# OpenEarable-PCB-flex-2_0.net
KiCad netlist of a schematic drawn in EasyEDA Pro
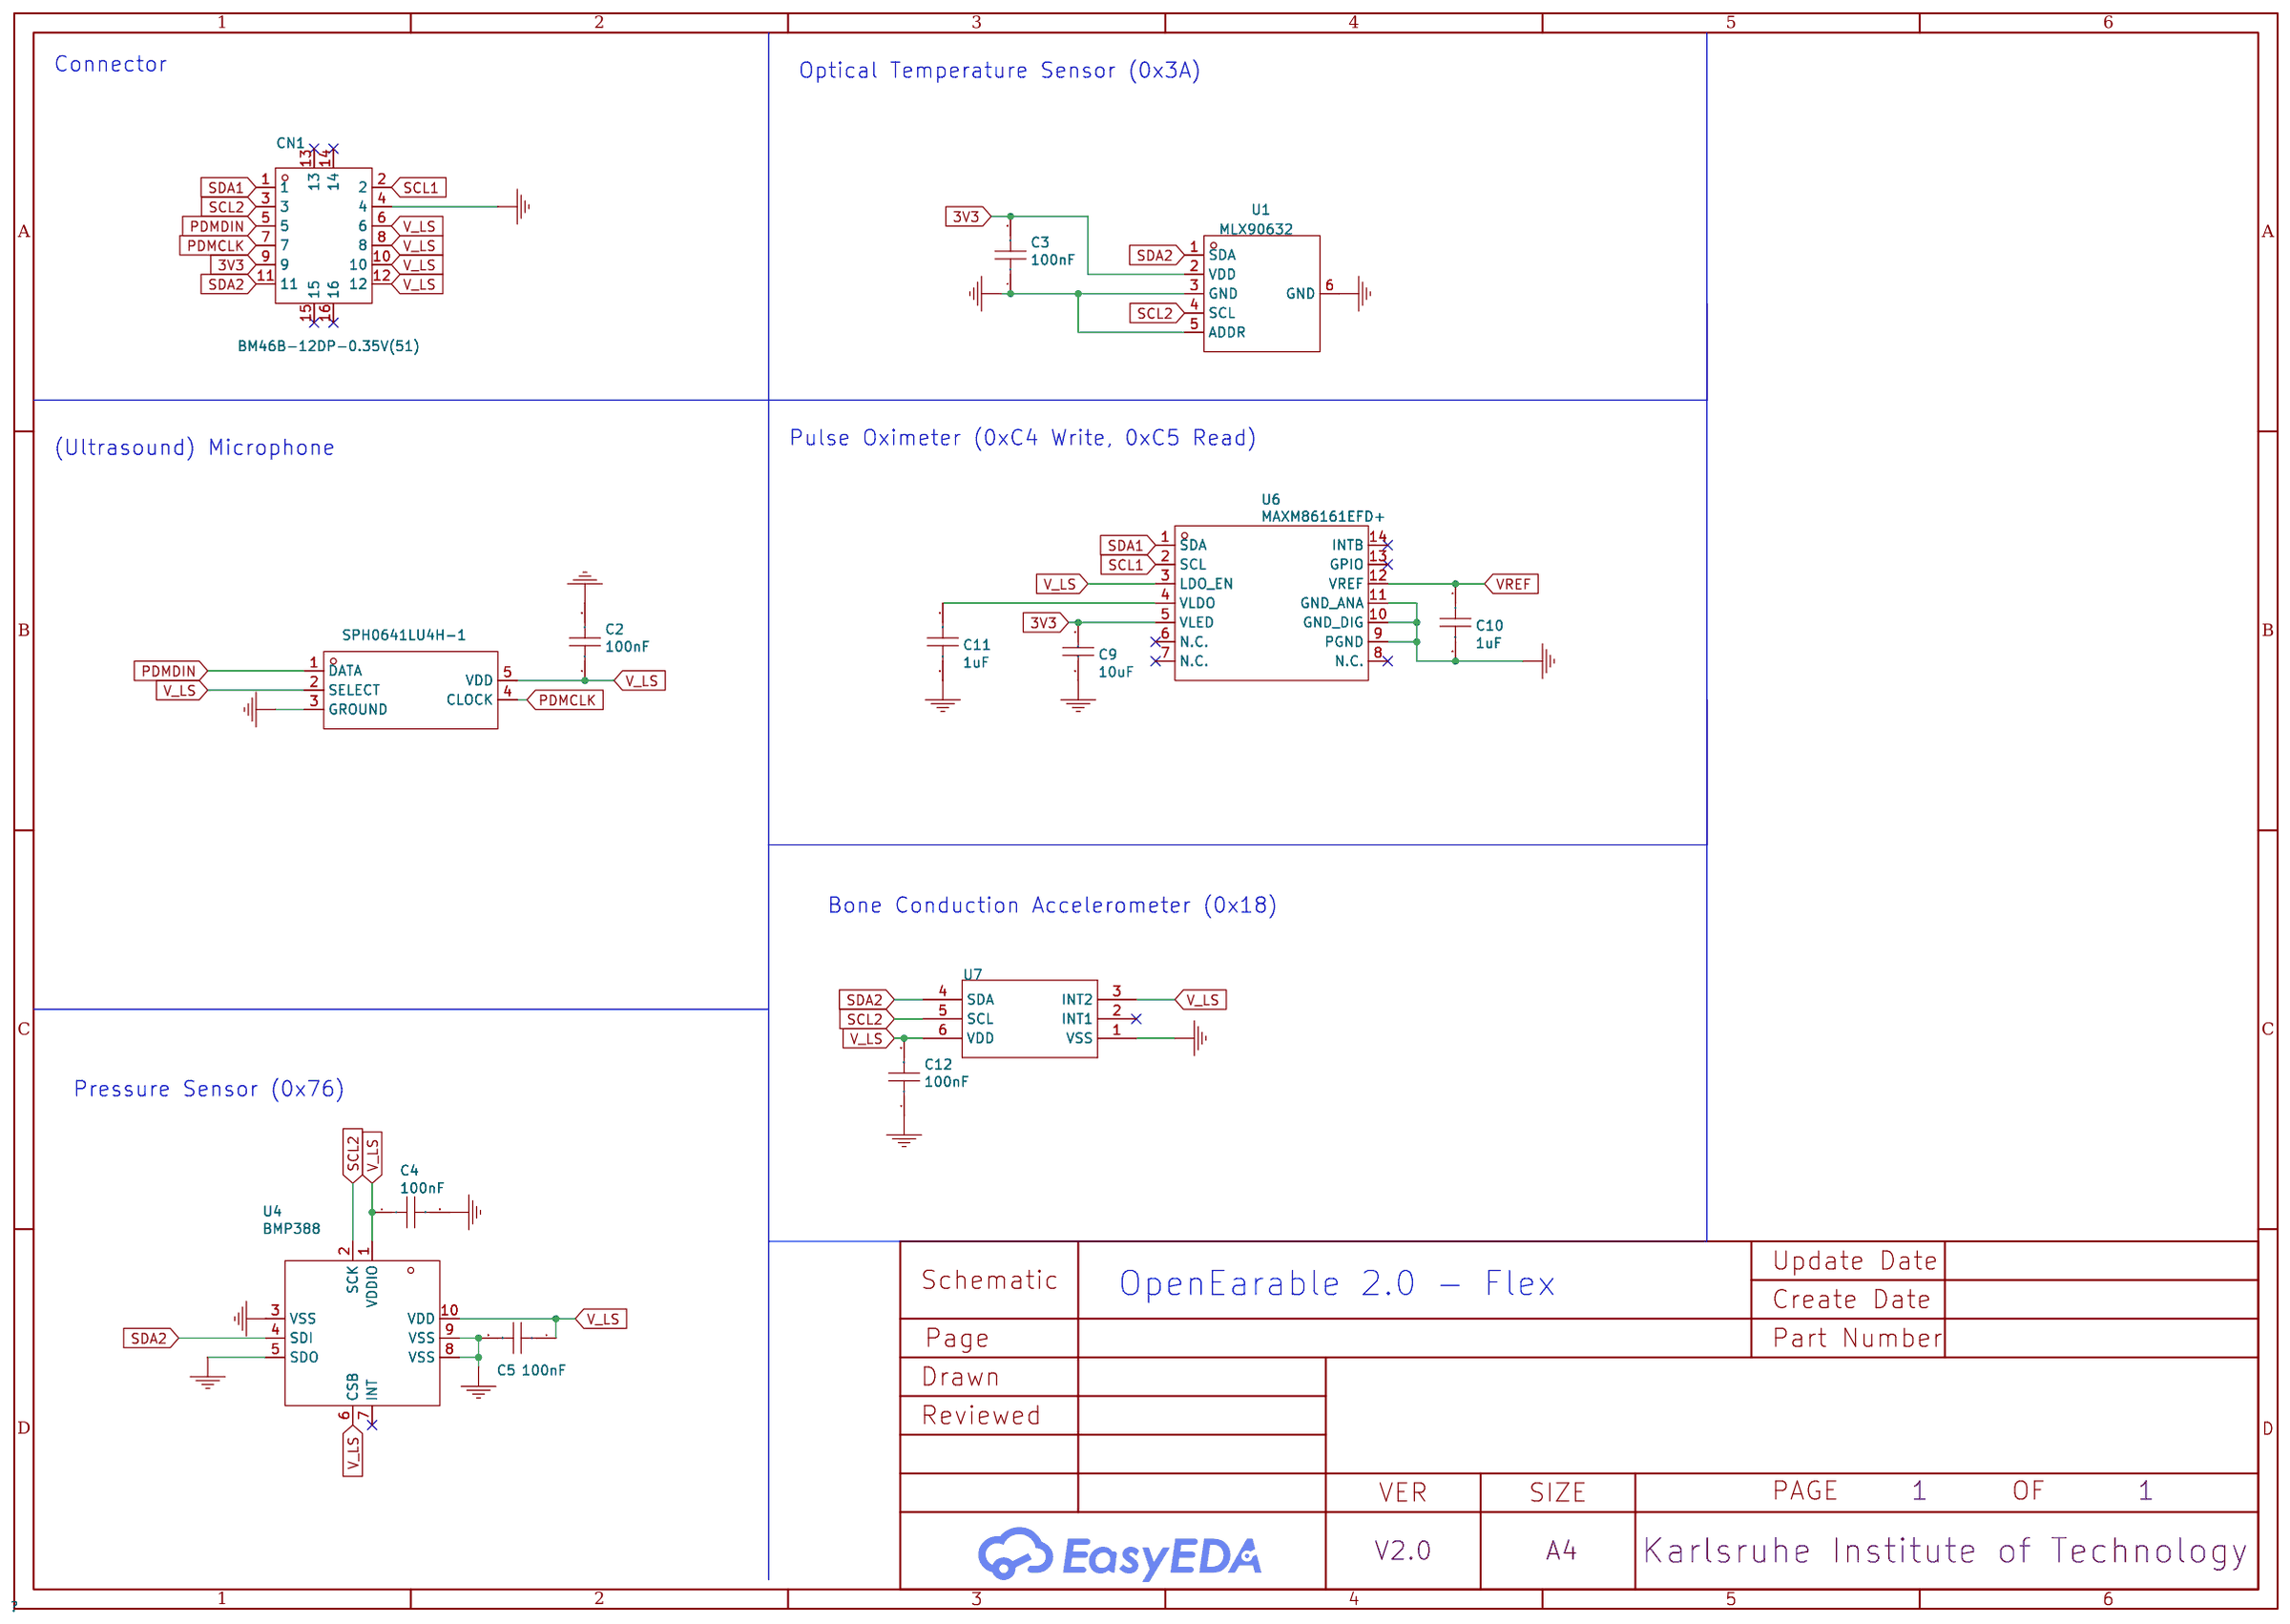
[diagram p0: schematic sheet]

(export (version "E")
  (design (tool "Eeschema 10.0.6"))
  (components
    (comp (ref "C2")
      (value "100nF")
      (footprint "easyedapro:C0201")
      (fields
        (field (name "Manufacturer Part") "TCC0201X5R104M6R3ZT")
        (field (name "Manufacturer") "CCTC(三环)")
      )
      (libsource (lib "easyedapro") (part "100nF"))
    )
    (comp (ref "C3")
      (value "100nF")
      (footprint "easyedapro:C0201")
      (fields
        (field (name "Manufacturer Part") "TCC0201X5R104M6R3ZT")
        (field (name "Manufacturer") "CCTC(三环)")
      )
      (libsource (lib "easyedapro") (part "100nF"))
    )
    (comp (ref "C4")
      (value "100nF")
      (footprint "easyedapro:C0201")
      (fields
        (field (name "Manufacturer Part") "TCC0201X5R104M6R3ZT")
        (field (name "Manufacturer") "CCTC(三环)")
      )
      (libsource (lib "easyedapro") (part "100nF"))
    )
    (comp (ref "C5")
      (value "100nF")
      (footprint "easyedapro:C0201")
      (fields
        (field (name "Manufacturer Part") "TCC0201X5R104M6R3ZT")
        (field (name "Manufacturer") "CCTC(三环)")
      )
      (libsource (lib "easyedapro") (part "100nF"))
    )
    (comp (ref "C9")
      (value "10uF")
      (footprint "easyedapro:C0402")
      (fields
        (field (name "Manufacturer Part") "CL05A106MQ5NUNC")
        (field (name "Manufacturer") "SAMSUNG(三星)")
      )
      (libsource (lib "easyedapro") (part "10uF"))
    )
    (comp (ref "C10")
      (value "1uF")
      (footprint "easyedapro:C0201")
      (fields
        (field (name "Manufacturer Part") "C0201X5R105M6R3NT")
        (field (name "Manufacturer") "SANYEAR(叁叶源)")
      )
      (libsource (lib "easyedapro") (part "1uF"))
    )
    (comp (ref "C11")
      (value "1uF")
      (footprint "easyedapro:C0201")
      (fields
        (field (name "Manufacturer Part") "C0201X5R105M6R3NT")
        (field (name "Manufacturer") "SANYEAR(叁叶源)")
      )
      (libsource (lib "easyedapro") (part "1uF"))
    )
    (comp (ref "C12")
      (value "100nF")
      (footprint "easyedapro:C0201")
      (fields
        (field (name "Manufacturer Part") "TCC0201X5R104M6R3ZT")
        (field (name "Manufacturer") "CCTC(三环)")
      )
      (libsource (lib "easyedapro") (part "100nF"))
    )
    (comp (ref "CN1")
      (value "BM46B-12DP-0.35V(51)")
      (footprint "easyedapro:CONN-SMD_12P-P0.35_BM46B-12DP-0.35V-51")
      (description "Number of Pins:- Pitch:0.35mm Mounting Style:Standing paste Number of Rows:2 Contact Plating:Gold")
      (fields (field (name "Manufacturer") "HRS(广濑)"))
      (libsource (lib "easyedapro") (part "BM46B-12DP-0.35V(51)"))
    )
    (comp (ref "U1")
      (value "MLX90632")
      (footprint "easyedapro:SENSOR-SMD_MLX90632")
      (libsource (lib "easyedapro") (part "MLX90632"))
    )
    (comp (ref "U3")
      (value "SPH0641LU4H-1")
      (footprint "easyedapro:MIC-SMD_5P_L3.5-W2.7-P0.82_SPH0641LU4H-1")
      (fields (field (name "Manufacturer Part") "sph0641lu4h-1"))
      (libsource (lib "easyedapro") (part "SPH0641LU4H-1"))
    )
    (comp (ref "U4")
      (value "BMP388")
      (footprint "easyedapro:SENSORM-SMD_BMP388")
      (fields (field (name "Manufacturer") "Bosch(博世)"))
      (libsource (lib "easyedapro") (part "BMP388"))
    )
    (comp (ref "U6")
      (value "MAXM86161EFD+")
      (footprint "easyedapro:OLGA-14_L4.3-W2.9-P0.60-TL")
      (fields (field (name "Manufacturer") "MAXIM(美信)"))
      (libsource (lib "easyedapro") (part "MAXM86161EFD+"))
    )
    (comp (ref "U7")
      (value "~")
      (footprint "easyedapro:BMA580")
      (libsource (lib "easyedapro") (part "BMA580"))
    )
  )
  (nets
    (net (code "1") (name "3V3") (class "Default")
      (node (ref "C3") (pin "2") (pinfunction "2_2") (pintype "unspecified"))
      (node (ref "C9") (pin "1") (pinfunction "1_1") (pintype "input"))
      (node (ref "CN1") (pin "9") (pinfunction "9_9") (pintype "unspecified"))
      (node (ref "U1") (pin "2") (pinfunction "VDD_2") (pintype "unspecified"))
      (node (ref "U6") (pin "5") (pinfunction "VLED_5") (pintype "unspecified"))
    )
    (net (code "2") (name "GND") (class "Default")
      (node (ref "C10") (pin "2") (pinfunction "2_2") (pintype "unspecified"))
      (node (ref "C11") (pin "2") (pinfunction "2_2") (pintype "unspecified"))
      (node (ref "C12") (pin "1") (pinfunction "1_1") (pintype "unspecified"))
      (node (ref "C2") (pin "2") (pinfunction "2_2") (pintype "unspecified"))
      (node (ref "C3") (pin "1") (pinfunction "1_1") (pintype "unspecified"))
      (node (ref "C4") (pin "2") (pinfunction "2_2") (pintype "unspecified"))
      (node (ref "C5") (pin "2") (pinfunction "2_2") (pintype "unspecified"))
      (node (ref "C9") (pin "2") (pinfunction "2_2") (pintype "input"))
      (node (ref "CN1") (pin "4") (pinfunction "4_4") (pintype "unspecified"))
      (node (ref "U1") (pin "3") (pinfunction "GND_3") (pintype "unspecified"))
      (node (ref "U1") (pin "5") (pinfunction "ADDR_5") (pintype "unspecified"))
      (node (ref "U1") (pin "6") (pinfunction "GND_6") (pintype "unspecified"))
      (node (ref "U3") (pin "3") (pinfunction "GROUND_3") (pintype "unspecified"))
      (node (ref "U4") (pin "3") (pinfunction "VSS_3") (pintype "unspecified"))
      (node (ref "U4") (pin "5") (pinfunction "SDO_5") (pintype "unspecified"))
      (node (ref "U4") (pin "8") (pinfunction "VSS_8") (pintype "unspecified"))
      (node (ref "U4") (pin "9") (pinfunction "VSS_9") (pintype "unspecified"))
      (node (ref "U6") (pin "10") (pinfunction "GND_DIG_10") (pintype "unspecified"))
      (node (ref "U6") (pin "11") (pinfunction "GND_ANA_11") (pintype "unspecified"))
      (node (ref "U6") (pin "9") (pinfunction "PGND_9") (pintype "unspecified"))
      (node (ref "U7") (pin "1") (pinfunction "VSS_1") (pintype "bidirectional"))
    )
    (net (code "3") (name "Net-(U6-VLDO)") (class "Default")
      (node (ref "C11") (pin "1") (pinfunction "1_1") (pintype "unspecified"))
      (node (ref "U6") (pin "4") (pinfunction "VLDO_4") (pintype "unspecified"))
    )
    (net (code "4") (name "PDMCLK") (class "Default")
      (node (ref "CN1") (pin "7") (pinfunction "7_7") (pintype "unspecified"))
      (node (ref "U3") (pin "4") (pinfunction "CLOCK_4") (pintype "unspecified"))
    )
    (net (code "5") (name "PDMDIN") (class "Default")
      (node (ref "CN1") (pin "5") (pinfunction "5_5") (pintype "unspecified"))
      (node (ref "U3") (pin "1") (pinfunction "DATA_1") (pintype "unspecified"))
    )
    (net (code "6") (name "SCL1") (class "Default")
      (node (ref "CN1") (pin "2") (pinfunction "2_2") (pintype "unspecified"))
      (node (ref "U6") (pin "2") (pinfunction "SCL_2") (pintype "unspecified"))
    )
    (net (code "7") (name "SCL2") (class "Default")
      (node (ref "CN1") (pin "3") (pinfunction "3_3") (pintype "unspecified"))
      (node (ref "U1") (pin "4") (pinfunction "SCL_4") (pintype "unspecified"))
      (node (ref "U4") (pin "2") (pinfunction "SCK_2") (pintype "unspecified"))
      (node (ref "U7") (pin "5") (pinfunction "SCL_5") (pintype "bidirectional"))
    )
    (net (code "8") (name "SDA1") (class "Default")
      (node (ref "CN1") (pin "1") (pinfunction "1_1") (pintype "unspecified"))
      (node (ref "U6") (pin "1") (pinfunction "SDA_1") (pintype "unspecified"))
    )
    (net (code "9") (name "SDA2") (class "Default")
      (node (ref "CN1") (pin "11") (pinfunction "11_11") (pintype "unspecified"))
      (node (ref "U1") (pin "1") (pinfunction "SDA_1") (pintype "unspecified"))
      (node (ref "U4") (pin "4") (pinfunction "SDI_4") (pintype "unspecified"))
      (node (ref "U7") (pin "4") (pinfunction "SDA_4") (pintype "bidirectional"))
    )
    (net (code "10") (name "VREF") (class "Default")
      (node (ref "C10") (pin "1") (pinfunction "1_1") (pintype "unspecified"))
      (node (ref "U6") (pin "12") (pinfunction "VREF_12") (pintype "unspecified"))
    )
    (net (code "11") (name "V_LS") (class "Default")
      (node (ref "C12") (pin "2") (pinfunction "2_2") (pintype "unspecified"))
      (node (ref "C2") (pin "1") (pinfunction "1_1") (pintype "unspecified"))
      (node (ref "C4") (pin "1") (pinfunction "1_1") (pintype "unspecified"))
      (node (ref "C5") (pin "1") (pinfunction "1_1") (pintype "unspecified"))
      (node (ref "CN1") (pin "10") (pinfunction "10_10") (pintype "unspecified"))
      (node (ref "CN1") (pin "12") (pinfunction "12_12") (pintype "unspecified"))
      (node (ref "CN1") (pin "6") (pinfunction "6_6") (pintype "unspecified"))
      (node (ref "CN1") (pin "8") (pinfunction "8_8") (pintype "unspecified"))
      (node (ref "U3") (pin "2") (pinfunction "SELECT_2") (pintype "unspecified"))
      (node (ref "U3") (pin "5") (pinfunction "VDD_5") (pintype "unspecified"))
      (node (ref "U4") (pin "1") (pinfunction "VDDIO_1") (pintype "unspecified"))
      (node (ref "U4") (pin "10") (pinfunction "VDD_10") (pintype "unspecified"))
      (node (ref "U4") (pin "6") (pinfunction "CSB_6") (pintype "unspecified"))
      (node (ref "U6") (pin "3") (pinfunction "LDO_EN_3") (pintype "unspecified"))
      (node (ref "U7") (pin "3") (pinfunction "INT2_3") (pintype "bidirectional"))
      (node (ref "U7") (pin "6") (pinfunction "VDD_6") (pintype "bidirectional"))
    )
    (net (code "12") (name "unconnected-(CN1-Pad13)") (class "Default")
      (node (ref "CN1") (pin "13") (pinfunction "13_13") (pintype "unspecified+no_connect"))
    )
    (net (code "13") (name "unconnected-(CN1-Pad14)") (class "Default")
      (node (ref "CN1") (pin "14") (pinfunction "14_14") (pintype "unspecified+no_connect"))
    )
    (net (code "14") (name "unconnected-(CN1-Pad15)") (class "Default")
      (node (ref "CN1") (pin "15") (pinfunction "15_15") (pintype "unspecified+no_connect"))
    )
    (net (code "15") (name "unconnected-(CN1-Pad16)") (class "Default")
      (node (ref "CN1") (pin "16") (pinfunction "16_16") (pintype "unspecified+no_connect"))
    )
    (net (code "16") (name "unconnected-(U4-INT-Pad7)") (class "Default")
      (node (ref "U4") (pin "7") (pinfunction "INT_7") (pintype "unspecified+no_connect"))
    )
    (net (code "17") (name "unconnected-(U6-GPIO-Pad13)") (class "Default")
      (node (ref "U6") (pin "13") (pinfunction "GPIO_13") (pintype "unspecified+no_connect"))
    )
    (net (code "18") (name "unconnected-(U6-INTB-Pad14)") (class "Default")
      (node (ref "U6") (pin "14") (pinfunction "INTB_14") (pintype "unspecified+no_connect"))
    )
    (net (code "19") (name "unconnected-(U6-N.C.-Pad6)") (class "Default")
      (node (ref "U6") (pin "6") (pinfunction "N.C._6") (pintype "unspecified+no_connect"))
    )
    (net (code "20") (name "unconnected-(U6-N.C.-Pad7)") (class "Default")
      (node (ref "U6") (pin "7") (pinfunction "N.C._7") (pintype "unspecified+no_connect"))
    )
    (net (code "21") (name "unconnected-(U6-N.C.-Pad8)") (class "Default")
      (node (ref "U6") (pin "8") (pinfunction "N.C._8") (pintype "unspecified+no_connect"))
    )
    (net (code "22") (name "unconnected-(U7-INT1-Pad2)") (class "Default")
      (node (ref "U7") (pin "2") (pinfunction "INT1_2") (pintype "bidirectional+no_connect"))
    )
  )
)
